# IO_FMU3_REV_G.net
KiCad netlist of a schematic drawn in Altium Designer
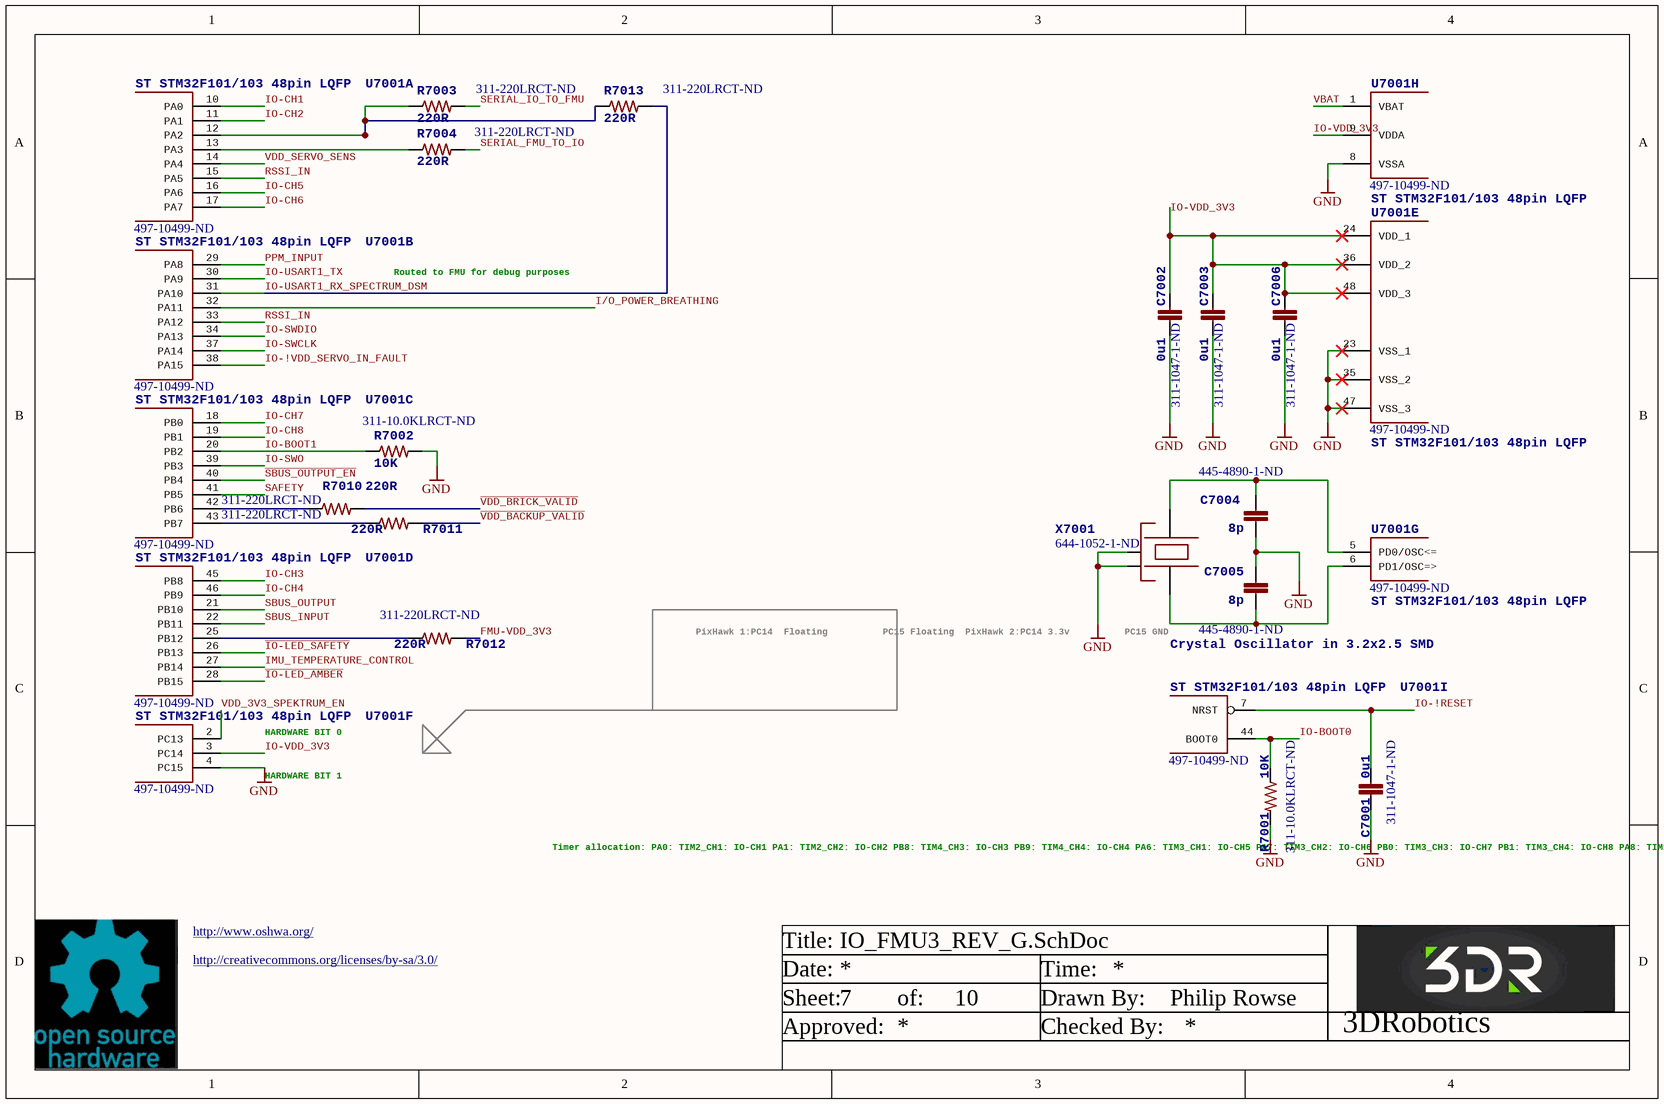
[diagram p0: IO_FMU3_REV_G.SchDoc]

(export (version "E")
  (design (tool "Eeschema 10.0.6"))
  (components
    (comp (ref "C7001")
      (value "0u1")
      (footprint "0402-CAP")
      (description "CAP CER 0.1UF 16V Y5V 0402")
      (fields
        (field (name "PARTNO") "CC0402ZRY5V7BB104")
        (field (name "SUPPLIER PART NUMBER 1") "311-1047-1-ND")
        (field (name "3DR_PARTNO") "ECM0700")
      )
      (libsource (lib "") (part "CAP0402_1"))
    )
    (comp (ref "C7002")
      (value "0u1")
      (footprint "0402-CAP")
      (description "CAP CER 0.1UF 16V Y5V 0402")
      (fields
        (field (name "PARTNO") "CC0402ZRY5V7BB104")
        (field (name "SUPPLIER PART NUMBER 1") "311-1047-1-ND")
        (field (name "3DR_PARTNO") "ECM0700")
      )
      (libsource (lib "pixhawk2") (part "CAP0402"))
    )
    (comp (ref "C7003")
      (value "0u1")
      (footprint "0402-CAP")
      (description "CAP CER 0.1UF 16V Y5V 0402")
      (fields
        (field (name "PARTNO") "CC0402ZRY5V7BB104")
        (field (name "SUPPLIER PART NUMBER 1") "311-1047-1-ND")
        (field (name "3DR_PARTNO") "ECM0700")
      )
      (libsource (lib "pixhawk2") (part "CAP0402"))
    )
    (comp (ref "C7004")
      (value "8p")
      (footprint "0402-CAP")
      (description "CAP CER 8PF 50V C0G 0402")
      (fields
        (field (name "PARTNO") "C1005C0G1H080C")
        (field (name "SUPPLIER PART NUMBER 1") "445-4890-1-ND")
        (field (name "3DR_PARTNO") "ECM0710")
      )
      (libsource (lib "pixhawk2") (part "CAP0402"))
    )
    (comp (ref "C7005")
      (value "8p")
      (footprint "0402-CAP")
      (description "CAP CER 8PF 50V C0G 0402")
      (fields
        (field (name "PARTNO") "C1005C0G1H080C")
        (field (name "SUPPLIER PART NUMBER 1") "445-4890-1-ND")
        (field (name "3DR_PARTNO") "ECM0710")
      )
      (libsource (lib "pixhawk2") (part "CAP0402"))
    )
    (comp (ref "C7006")
      (value "0u1")
      (footprint "0402-CAP")
      (description "CAP CER 0.1UF 16V Y5V 0402")
      (fields
        (field (name "PARTNO") "CC0402ZRY5V7BB104")
        (field (name "SUPPLIER PART NUMBER 1") "311-1047-1-ND")
        (field (name "3DR_PARTNO") "ECM0700")
      )
      (libsource (lib "pixhawk2") (part "CAP0402"))
    )
    (comp (ref "R7001")
      (value "10K")
      (footprint "0402-RES")
      (description "RES 10K OHM 1/16W 1% 0402 SMD")
      (fields
        (field (name "PARTNO") "RC0402FR-0710KL")
        (field (name "SUPPLIER PART NUMBER 1") "311-10.0KLRCT-ND")
        (field (name "3DR_PARTNO") "ECM0800")
      )
      (libsource (lib "pixhawk2") (part "RESISTOR0402-RES"))
    )
    (comp (ref "R7002")
      (value "10K")
      (footprint "0402-RES")
      (description "RES 10K OHM 1/16W 1% 0402 SMD")
      (fields
        (field (name "PARTNO") "RC0402FR-0710KL")
        (field (name "SUPPLIER PART NUMBER 1") "311-10.0KLRCT-ND")
        (field (name "3DR_PARTNO") "ECM0800")
      )
      (libsource (lib "pixhawk2") (part "RESISTOR0402-RES"))
    )
    (comp (ref "R7003")
      (value "220R")
      (footprint "0402-RES")
      (description "RES 220 OHM 1/16W 1% 0402 SMD")
      (fields
        (field (name "PARTNO") "RC0402FR-07220RL")
        (field (name "SUPPLIER PART NUMBER 1") "311-220LRCT-ND")
        (field (name "3DR_PARTNO") "ECM0821")
      )
      (libsource (lib "pixhawk2") (part "RESISTOR0402-RES"))
    )
    (comp (ref "R7004")
      (value "220R")
      (footprint "0402-RES")
      (description "RES 220 OHM 1/16W 1% 0402 SMD")
      (fields
        (field (name "PARTNO") "RC0402FR-07220RL")
        (field (name "SUPPLIER PART NUMBER 1") "311-220LRCT-ND")
        (field (name "3DR_PARTNO") "ECM0821")
      )
      (libsource (lib "pixhawk2") (part "RESISTOR0402-RES"))
    )
    (comp (ref "R7010")
      (value "220R")
      (footprint "0402-RES")
      (description "RES 220 OHM 1/16W 1% 0402 SMD")
      (fields
        (field (name "PARTNO") "RC0402FR-07220RL")
        (field (name "SUPPLIER PART NUMBER 1") "311-220LRCT-ND")
        (field (name "3DR_PARTNO") "ECM0821")
      )
      (libsource (lib "pixhawk2") (part "RESISTOR0402-RES"))
    )
    (comp (ref "R7011")
      (value "220R")
      (footprint "0402-RES")
      (description "RES 220 OHM 1/16W 1% 0402 SMD")
      (fields
        (field (name "PARTNO") "RC0402FR-07220RL")
        (field (name "SUPPLIER PART NUMBER 1") "311-220LRCT-ND")
        (field (name "3DR_PARTNO") "ECM0821")
      )
      (libsource (lib "pixhawk2") (part "RESISTOR0402-RES"))
    )
    (comp (ref "R7012")
      (value "220R")
      (footprint "0402-RES")
      (description "RES 220 OHM 1/16W 1% 0402 SMD")
      (fields
        (field (name "PARTNO") "RC0402FR-07220RL")
        (field (name "SUPPLIER PART NUMBER 1") "311-220LRCT-ND")
        (field (name "3DR_PARTNO") "ECM0821")
      )
      (libsource (lib "pixhawk2") (part "RESISTOR0402-RES"))
    )
    (comp (ref "R7013")
      (value "220R")
      (footprint "0402-RES")
      (description "RES 220 OHM 1/16W 1% 0402 SMD")
      (fields
        (field (name "PARTNO") "RC0402FR-07220RL")
        (field (name "SUPPLIER PART NUMBER 1") "311-220LRCT-ND")
        (field (name "3DR_PARTNO") "ECM0821")
      )
      (libsource (lib "pixhawk2") (part "RESISTOR0402-RES"))
    )
    (comp (ref "U7001")
      (value "ST STM32F101/103 48pin LQFP")
      (footprint "TQFP48")
      (description "MCU 32BIT ARM 64K FLASH 48LQFP")
      (fields (field (name "SUPPLIER PART NUMBER 1") "497-10499-ND") (field (name "3DR_PARTNO") "EMC0842"))
      (libsource (lib "pixhawk2") (part "STM32F10XCXT6"))
    )
    (comp (ref "X7001")
      (value "Crystal Oscillator in 3.2x2.5 SMD")
      (footprint "OSCILLATOR-3.2X2.5")
      (description "CRYSTAL 24MHZ 8PF SMD")
      (fields
        (field (name "SUPPLIER PART NUMBER 1") "644-1052-1-ND")
        (field (name "3DR_PARTNO") "ECM0708")
        (field (name "PARTNO") "NX3225SA-24.000MHZ-STD-CSR-1")
      )
      (libsource (lib "pixhawk2") (part "OSCILLATOR-3.2X2.5"))
    )
  )
  (nets
    (net (code "1") (name "/FMU-VDD_3V3") (class "Default")
      (node (ref "R7012") (pin "P$2") (pinfunction "2_P$2") (pintype "passive"))
    )
    (net (code "2") (name "/IMU_TEMPERATURE_CONTROL") (class "Default")
      (node (ref "U7001") (pin "27") (pinfunction "PB14_27") (pintype "passive"))
    )
    (net (code "3") (name "/IO-!RESET") (class "Default")
      (node (ref "C7001") (pin "P$2") (pinfunction "2_P$2") (pintype "passive"))
      (node (ref "U7001") (pin "7") (pinfunction "NRST_7") (pintype "passive"))
    )
    (net (code "4") (name "/IO-!VDD_SERVO_IN_FAULT") (class "Default")
      (node (ref "U7001") (pin "38") (pinfunction "PA15_38") (pintype "passive"))
    )
    (net (code "5") (name "/IO-BOOT0") (class "Default")
      (node (ref "R7001") (pin "P$1") (pinfunction "1_P$1") (pintype "passive"))
      (node (ref "U7001") (pin "44") (pinfunction "BOOT0_44") (pintype "passive"))
    )
    (net (code "6") (name "/IO-BOOT1") (class "Default")
      (node (ref "R7002") (pin "P$1") (pinfunction "1_P$1") (pintype "passive"))
      (node (ref "U7001") (pin "20") (pinfunction "PB2_20") (pintype "passive"))
    )
    (net (code "7") (name "/IO-CH1") (class "Default")
      (node (ref "U7001") (pin "10") (pinfunction "PA0_10") (pintype "passive"))
    )
    (net (code "8") (name "/IO-CH2") (class "Default")
      (node (ref "U7001") (pin "11") (pinfunction "PA1_11") (pintype "passive"))
    )
    (net (code "9") (name "/IO-CH3") (class "Default")
      (node (ref "U7001") (pin "45") (pinfunction "PB8_45") (pintype "passive"))
    )
    (net (code "10") (name "/IO-CH4") (class "Default")
      (node (ref "U7001") (pin "46") (pinfunction "PB9_46") (pintype "passive"))
    )
    (net (code "11") (name "/IO-CH5") (class "Default")
      (node (ref "U7001") (pin "16") (pinfunction "PA6_16") (pintype "passive"))
    )
    (net (code "12") (name "/IO-CH6") (class "Default")
      (node (ref "U7001") (pin "17") (pinfunction "PA7_17") (pintype "passive"))
    )
    (net (code "13") (name "/IO-CH7") (class "Default")
      (node (ref "U7001") (pin "18") (pinfunction "PB0_18") (pintype "passive"))
    )
    (net (code "14") (name "/IO-CH8") (class "Default")
      (node (ref "U7001") (pin "19") (pinfunction "PB1_19") (pintype "passive"))
    )
    (net (code "15") (name "/IO-SWCLK") (class "Default")
      (node (ref "U7001") (pin "37") (pinfunction "PA14_37") (pintype "passive"))
    )
    (net (code "16") (name "/IO-SWDIO") (class "Default")
      (node (ref "U7001") (pin "34") (pinfunction "PA13_34") (pintype "passive"))
    )
    (net (code "17") (name "/IO-SWO") (class "Default")
      (node (ref "U7001") (pin "39") (pinfunction "PB3_39") (pintype "passive"))
    )
    (net (code "18") (name "/IO-USART1_RX_SPECTRUM_DSM") (class "Default")
      (node (ref "R7013") (pin "P$2") (pinfunction "2_P$2") (pintype "passive"))
      (node (ref "U7001") (pin "31") (pinfunction "PA10_31") (pintype "passive"))
    )
    (net (code "19") (name "/IO-USART1_TX") (class "Default")
      (node (ref "U7001") (pin "30") (pinfunction "PA9_30") (pintype "passive"))
    )
    (net (code "20") (name "/IO-VDD_3V3") (class "Default")
      (node (ref "C7002") (pin "P$1") (pinfunction "1_P$1") (pintype "passive"))
      (node (ref "C7003") (pin "P$1") (pinfunction "1_P$1") (pintype "passive"))
      (node (ref "C7006") (pin "P$1") (pinfunction "1_P$1") (pintype "passive"))
      (node (ref "U7001") (pin "24") (pinfunction "VDD_1_24") (pintype "power_in"))
      (node (ref "U7001") (pin "3") (pinfunction "PC14_3") (pintype "passive"))
      (node (ref "U7001") (pin "36") (pinfunction "VDD_2_36") (pintype "power_in"))
      (node (ref "U7001") (pin "48") (pinfunction "VDD_3_48") (pintype "power_in"))
      (node (ref "U7001") (pin "9") (pinfunction "VDDA_9") (pintype "power_in"))
    )
    (net (code "21") (name "/I{slash}O_POWER_BREATHING") (class "Default")
      (node (ref "U7001") (pin "32") (pinfunction "PA11_32") (pintype "passive"))
    )
    (net (code "22") (name "/PPM_INPUT") (class "Default")
      (node (ref "U7001") (pin "29") (pinfunction "PA8_29") (pintype "passive"))
    )
    (net (code "23") (name "/RSSI_IN") (class "Default")
      (node (ref "U7001") (pin "15") (pinfunction "PA5_15") (pintype "passive"))
      (node (ref "U7001") (pin "33") (pinfunction "PA12_33") (pintype "passive"))
    )
    (net (code "24") (name "/SAFETY") (class "Default")
      (node (ref "U7001") (pin "41") (pinfunction "PB5_41") (pintype "passive"))
    )
    (net (code "25") (name "/SBUS_INPUT") (class "Default")
      (node (ref "U7001") (pin "22") (pinfunction "PB11_22") (pintype "passive"))
    )
    (net (code "26") (name "/SBUS_OUTPUT") (class "Default")
      (node (ref "U7001") (pin "21") (pinfunction "PB10_21") (pintype "passive"))
    )
    (net (code "27") (name "/SERIAL_FMU_TO_IO") (class "Default")
      (node (ref "R7004") (pin "P$2") (pinfunction "2_P$2") (pintype "passive"))
    )
    (net (code "28") (name "/SERIAL_IO_TO_FMU") (class "Default")
      (node (ref "R7003") (pin "P$2") (pinfunction "2_P$2") (pintype "passive"))
    )
    (net (code "29") (name "/VBAT") (class "Default")
      (node (ref "U7001") (pin "1") (pinfunction "VBAT_1") (pintype "power_in"))
    )
    (net (code "30") (name "/VDD_3V3_SPEKTRUM_EN") (class "Default")
      (node (ref "U7001") (pin "2") (pinfunction "PC13_2") (pintype "passive"))
    )
    (net (code "31") (name "/VDD_SERVO_SENS") (class "Default")
      (node (ref "U7001") (pin "14") (pinfunction "PA4_14") (pintype "passive"))
    )
    (net (code "32") (name "/~{IO-LED_AMBER}") (class "Default")
      (node (ref "U7001") (pin "28") (pinfunction "PB15_28") (pintype "passive"))
    )
    (net (code "33") (name "/~{IO-LED_SAFETY}") (class "Default")
      (node (ref "U7001") (pin "26") (pinfunction "PB13_26") (pintype "passive"))
    )
    (net (code "34") (name "/~{SBUS_OUTPUT_EN}") (class "Default")
      (node (ref "U7001") (pin "40") (pinfunction "PB4_40") (pintype "passive"))
    )
    (net (code "35") (name "/~{VDD_BACKUP_VALID}") (class "Default")
      (node (ref "R7011") (pin "P$2") (pinfunction "2_P$2") (pintype "passive"))
    )
    (net (code "36") (name "/~{VDD_BRICK_VALID}") (class "Default")
      (node (ref "R7010") (pin "P$2") (pinfunction "2_P$2") (pintype "passive"))
    )
    (net (code "37") (name "GND") (class "Default")
      (node (ref "C7001") (pin "P$1") (pinfunction "1_P$1") (pintype "passive"))
      (node (ref "C7002") (pin "P$2") (pinfunction "2_P$2") (pintype "passive"))
      (node (ref "C7003") (pin "P$2") (pinfunction "2_P$2") (pintype "passive"))
      (node (ref "C7004") (pin "P$2") (pinfunction "2_P$2") (pintype "passive"))
      (node (ref "C7005") (pin "P$1") (pinfunction "1_P$1") (pintype "passive"))
      (node (ref "C7006") (pin "P$2") (pinfunction "2_P$2") (pintype "passive"))
      (node (ref "R7001") (pin "P$2") (pinfunction "2_P$2") (pintype "passive"))
      (node (ref "R7002") (pin "P$2") (pinfunction "2_P$2") (pintype "passive"))
      (node (ref "U7001") (pin "23") (pinfunction "VSS_1_23") (pintype "power_in"))
      (node (ref "U7001") (pin "35") (pinfunction "VSS_2_35") (pintype "power_in"))
      (node (ref "U7001") (pin "4") (pinfunction "PC15_4") (pintype "passive"))
      (node (ref "U7001") (pin "47") (pinfunction "VSS_3_47") (pintype "power_in"))
      (node (ref "U7001") (pin "8") (pinfunction "VSSA_8") (pintype "power_in"))
      (node (ref "X7001") (pin "2") (pinfunction "NC_2_2") (pintype "open_emitter"))
      (node (ref "X7001") (pin "4") (pinfunction "NC_4_4") (pintype "open_emitter"))
    )
    (net (code "38") (name "Net-(C7004-1)") (class "Default")
      (node (ref "C7004") (pin "P$1") (pinfunction "1_P$1") (pintype "passive"))
      (node (ref "U7001") (pin "5") (pinfunction "PD0/OSC<=_5") (pintype "passive"))
      (node (ref "X7001") (pin "3") (pinfunction "3_3") (pintype "passive"))
    )
    (net (code "39") (name "Net-(C7005-2)") (class "Default")
      (node (ref "C7005") (pin "P$2") (pinfunction "2_P$2") (pintype "passive"))
      (node (ref "U7001") (pin "6") (pinfunction "PD1/OSC=>_6") (pintype "passive"))
      (node (ref "X7001") (pin "1") (pinfunction "1_1") (pintype "passive"))
    )
    (net (code "40") (name "Net-(R7003-1)") (class "Default")
      (node (ref "R7003") (pin "P$1") (pinfunction "1_P$1") (pintype "passive"))
      (node (ref "R7013") (pin "P$1") (pinfunction "1_P$1") (pintype "passive"))
      (node (ref "U7001") (pin "12") (pinfunction "PA2_12") (pintype "passive"))
    )
    (net (code "41") (name "Net-(R7004-1)") (class "Default")
      (node (ref "R7004") (pin "P$1") (pinfunction "1_P$1") (pintype "passive"))
      (node (ref "U7001") (pin "13") (pinfunction "PA3_13") (pintype "passive"))
    )
    (net (code "42") (name "Net-(R7010-1)") (class "Default")
      (node (ref "R7010") (pin "P$1") (pinfunction "1_P$1") (pintype "passive"))
      (node (ref "U7001") (pin "42") (pinfunction "PB6_42") (pintype "passive"))
    )
    (net (code "43") (name "Net-(R7011-1)") (class "Default")
      (node (ref "R7011") (pin "P$1") (pinfunction "1_P$1") (pintype "passive"))
      (node (ref "U7001") (pin "43") (pinfunction "PB7_43") (pintype "passive"))
    )
    (net (code "44") (name "Net-(R7012-1)") (class "Default")
      (node (ref "R7012") (pin "P$1") (pinfunction "1_P$1") (pintype "passive"))
      (node (ref "U7001") (pin "25") (pinfunction "PB12_25") (pintype "passive"))
    )
  )
)
